# OPTO.net
KiCad netlist of a schematic drawn in EAGLE
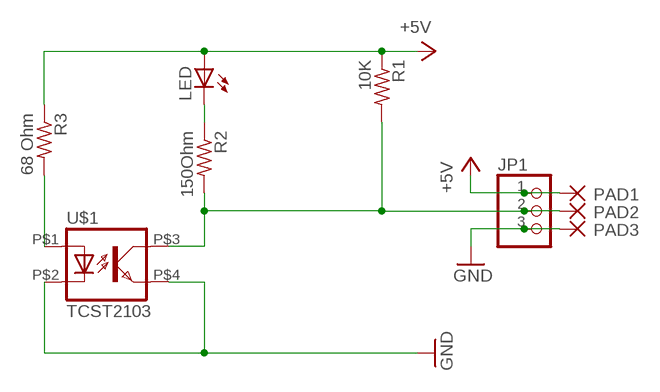
[diagram p0: schematic, sheet 1]

(export (version "E")
  (design (tool "Eeschema 10.0.6"))
  (components
    (comp (ref "JP1")
      (value "PINHD-1X3CB")
      (footprint "eagle-import:1X03-CLEANBIG")
      (libsource (lib "eagle-import") (part "PINHD-1X3CB"))
    )
    (comp (ref "LED")
      (value "LEDCHIPLED_0805")
      (footprint "eagle-import:CHIPLED_0805")
      (libsource (lib "eagle-import") (part "LEDCHIPLED_0805"))
    )
    (comp (ref "PAD1")
      (value "WIREPADSMD1,27-254")
      (footprint "eagle-import:SMD1,27-2,54")
      (libsource (lib "eagle-import") (part "WIREPADSMD1,27-254"))
    )
    (comp (ref "PAD2")
      (value "WIREPADSMD1,27-254")
      (footprint "eagle-import:SMD1,27-2,54")
      (libsource (lib "eagle-import") (part "WIREPADSMD1,27-254"))
    )
    (comp (ref "PAD3")
      (value "WIREPADSMD1,27-254")
      (footprint "eagle-import:SMD1,27-2,54")
      (libsource (lib "eagle-import") (part "WIREPADSMD1,27-254"))
    )
    (comp (ref "R1")
      (value "10K")
      (footprint "eagle-import:R0805")
      (libsource (lib "eagle-import") (part "R-US_R0805"))
    )
    (comp (ref "R2")
      (value "150Ohm")
      (footprint "eagle-import:R0805")
      (libsource (lib "eagle-import") (part "R-US_R0805"))
    )
    (comp (ref "R3")
      (value "68 Ohm")
      (footprint "eagle-import:R0805")
      (libsource (lib "eagle-import") (part "R-US_R0805"))
    )
    (comp (ref "U$1")
      (value "TCST2103")
      (footprint "eagle-import:TCST2103")
      (libsource (lib "eagle-import") (part "TCST2103"))
    )
  )
  (nets
    (net (code "1") (name "+5V") (class "Default")
      (node (ref "JP1") (pin "1") (pinfunction "1_1") (pintype "passive"))
      (node (ref "LED") (pin "A") (pinfunction "A_A") (pintype "passive"))
      (node (ref "PAD1") (pin "1") (pinfunction "P_1") (pintype "passive"))
      (node (ref "R1") (pin "1") (pinfunction "1_1") (pintype "passive"))
      (node (ref "R3") (pin "1") (pinfunction "1_1") (pintype "passive"))
    )
    (net (code "2") (name "GND") (class "Default")
      (node (ref "JP1") (pin "3") (pinfunction "3_3") (pintype "passive"))
      (node (ref "PAD3") (pin "1") (pinfunction "P_1") (pintype "passive"))
      (node (ref "U$1") (pin "P$2") (pinfunction "C_P$2") (pintype "passive"))
      (node (ref "U$1") (pin "P$4") (pinfunction "EMIT_P$4") (pintype "passive"))
    )
    (net (code "3") (name "Net-(LED-PadC)") (class "Default")
      (node (ref "LED") (pin "C") (pinfunction "C_C") (pintype "passive"))
      (node (ref "R2") (pin "1") (pinfunction "1_1") (pintype "passive"))
    )
    (net (code "4") (name "Net-(PAD2-P)") (class "Default")
      (node (ref "JP1") (pin "2") (pinfunction "2_2") (pintype "passive"))
      (node (ref "PAD2") (pin "1") (pinfunction "P_1") (pintype "passive"))
      (node (ref "R1") (pin "2") (pinfunction "2_2") (pintype "passive"))
      (node (ref "R2") (pin "2") (pinfunction "2_2") (pintype "passive"))
      (node (ref "U$1") (pin "P$3") (pinfunction "COL_P$3") (pintype "passive"))
    )
    (net (code "5") (name "Net-(U$1-A)") (class "Default")
      (node (ref "R3") (pin "2") (pinfunction "2_2") (pintype "passive"))
      (node (ref "U$1") (pin "P$1") (pinfunction "A_P$1") (pintype "passive"))
    )
  )
)
